# buz_schematic.net
KiCad netlist of a schematic drawn in Altium Designer
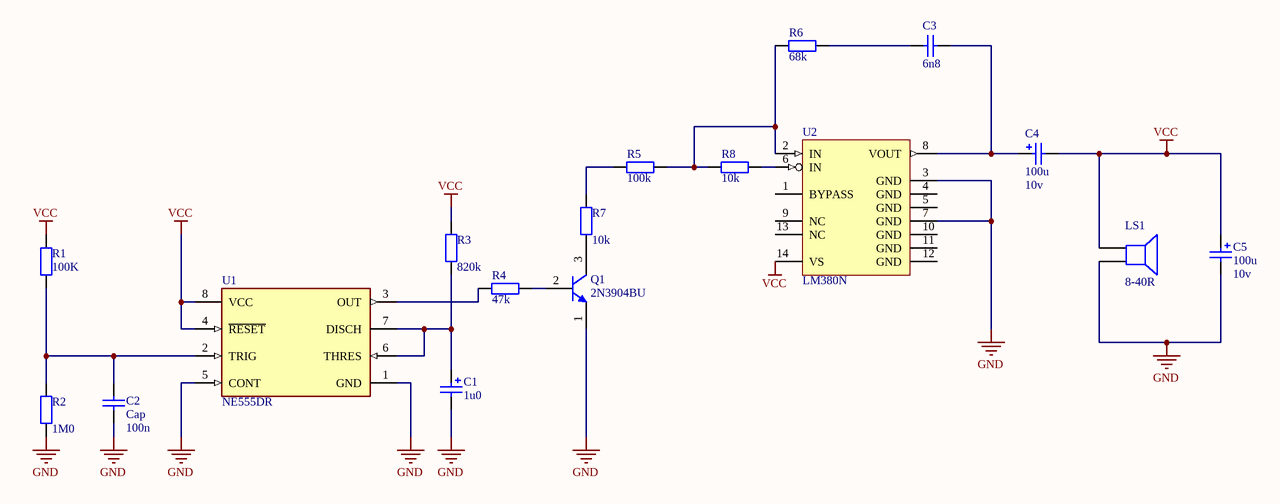
[diagram p0: buz_schematic.SchDoc]

(export (version "E")
  (design (tool "Eeschema 10.0.6"))
  (components
    (comp (ref "C1")
      (value "1u0")
      (footprint "RB7.6-15")
      (description "Polarized Capacitor (Radial)")
      (fields (field (name "PUBLISHER") "Altium Limited"))
      (libsource (lib "DBUZ_Integrated_Library") (part "Cap Pol1"))
    )
    (comp (ref "C2")
      (value "Cap")
      (footprint "RAD-0.3")
      (description "Capacitor")
      (fields (field (name "ALTIUM_VALUE") "100n") (field (name "PUBLISHER") "Altium Limited"))
      (libsource (lib "DBUZ_Integrated_Library") (part "Cap"))
    )
    (comp (ref "C3")
      (value "6n8")
      (footprint "RAD-0.3")
      (description "Capacitor")
      (fields (field (name "PUBLISHER") "Altium Limited"))
      (libsource (lib "DBUZ_Integrated_Library") (part "Cap"))
    )
    (comp (ref "C4")
      (value "100u")
      (footprint "RB7.6-15")
      (description "Polarized Capacitor (Radial)")
      (fields (field (name "ALTIUM_VALUE") "10v") (field (name "PUBLISHER") "Altium Limited"))
      (libsource (lib "DBUZ_Integrated_Library") (part "Cap Pol1"))
    )
    (comp (ref "C5")
      (value "100u")
      (footprint "RB7.6-15")
      (description "Polarized Capacitor (Radial)")
      (fields (field (name "ALTIUM_VALUE") "10v") (field (name "PUBLISHER") "Altium Limited"))
      (libsource (lib "DBUZ_Integrated_Library") (part "Cap Pol1"))
    )
    (comp (ref "LS1")
      (value "8-40R")
      (footprint "AXIAL-0.4")
      (description "Loudspeaker")
      (fields (field (name "PUBLISHER") "Altium Limited"))
      (libsource (lib "DBUZ_Integrated_Library") (part "Speaker"))
    )
    (comp (ref "Q1")
      (value "2N3904BU")
      (footprint "FAIR-TO-92")
      (description "NPN General-Purpose Amplifier, 40 V VCEO, 0.2 A, -55 to 150 degC, 2-Pin TO-92, RoHS, Bulk")
      (fields (field (name "MANUFACTURER") "FairchildSemiconductor"))
      (libsource (lib "DBUZ_Integrated_Library") (part "2N3904BU"))
    )
    (comp (ref "R1")
      (value "100K")
      (footprint "AXIAL-0.4")
      (description "Resistor")
      (fields (field (name "Comment") "Res2") (field (name "PUBLISHER") "Altium Limited"))
      (libsource (lib "") (part "Res2_2"))
    )
    (comp (ref "R2")
      (value "1M0")
      (footprint "AXIAL-0.4")
      (description "Resistor")
      (fields (field (name "Comment") "Res2") (field (name "PUBLISHER") "Altium Limited"))
      (libsource (lib "") (part "Res2_1"))
    )
    (comp (ref "R3")
      (value "820k")
      (footprint "AXIAL-0.4")
      (description "Resistor")
      (fields (field (name "Comment") "Res2") (field (name "PUBLISHER") "Altium Limited"))
      (libsource (lib "") (part "Res2_1"))
    )
    (comp (ref "R4")
      (value "47k")
      (footprint "AXIAL-0.4")
      (description "Resistor")
      (fields (field (name "Comment") "Res2") (field (name "PUBLISHER") "Altium Limited"))
      (libsource (lib "DBUZ_Integrated_Library") (part "Res2"))
    )
    (comp (ref "R5")
      (value "100k")
      (footprint "AXIAL-0.4")
      (description "Resistor")
      (fields (field (name "Comment") "Res2") (field (name "PUBLISHER") "Altium Limited"))
      (libsource (lib "DBUZ_Integrated_Library") (part "Res2"))
    )
    (comp (ref "R6")
      (value "68k")
      (footprint "AXIAL-0.4")
      (description "Resistor")
      (fields (field (name "Comment") "Res2") (field (name "PUBLISHER") "Altium Limited"))
      (libsource (lib "DBUZ_Integrated_Library") (part "Res2"))
    )
    (comp (ref "R7")
      (value "10k")
      (footprint "AXIAL-0.4")
      (description "Resistor")
      (fields (field (name "Comment") "Res2") (field (name "PUBLISHER") "Altium Limited"))
      (libsource (lib "") (part "Res2_1"))
    )
    (comp (ref "R8")
      (value "10k")
      (footprint "AXIAL-0.4")
      (description "Resistor")
      (fields (field (name "Comment") "Res2") (field (name "PUBLISHER") "Altium Limited"))
      (libsource (lib "DBUZ_Integrated_Library") (part "Res2"))
    )
    (comp (ref "U1")
      (value "NE555DR")
      (footprint "FP-D0008A-IPC_C")
      (description "IC OSC SGL TIMER 100KHZ 8-SOIC")
      (libsource (lib "DBUZ_Integrated_Library") (part "555"))
    )
    (comp (ref "U2")
      (value "LM380N")
      (footprint "N14A")
      (description "2.5W Audio Power Amplifier, 14-pin MDIP")
      (fields (field (name "MANUFACTURER") "National Semiconductor"))
      (libsource (lib "DB_ILib") (part "LM380N"))
    )
  )
  (nets
    (net (code "1") (name "GND") (class "Default")
      (node (ref "C1") (pin "2") (pinfunction "2_2") (pintype "passive"))
      (node (ref "C2") (pin "1") (pinfunction "1_1") (pintype "passive"))
      (node (ref "C5") (pin "2") (pinfunction "2_2") (pintype "passive"))
      (node (ref "LS1") (pin "2") (pinfunction "2_2") (pintype "passive"))
      (node (ref "Q1") (pin "1") (pinfunction "E_1") (pintype "passive"))
      (node (ref "R2") (pin "1") (pinfunction "1_1") (pintype "passive"))
      (node (ref "U1") (pin "1") (pinfunction "GND_1") (pintype "power_in"))
      (node (ref "U1") (pin "5") (pinfunction "CONT_5") (pintype "input"))
      (node (ref "U2") (pin "3") (pinfunction "GND_3") (pintype "power_in"))
      (node (ref "U2") (pin "7") (pinfunction "GND_7") (pintype "power_in"))
    )
    (net (code "2") (name "Net-(C3-Pad1)") (class "Default")
      (node (ref "C3") (pin "1") (pinfunction "1_1") (pintype "passive"))
      (node (ref "R6") (pin "1") (pinfunction "1_1") (pintype "passive"))
    )
    (net (code "3") (name "Net-(Q1-B)") (class "Default")
      (node (ref "Q1") (pin "2") (pinfunction "B_2") (pintype "passive"))
      (node (ref "R4") (pin "1") (pinfunction "1_1") (pintype "passive"))
    )
    (net (code "4") (name "Net-(Q1-C)") (class "Default")
      (node (ref "Q1") (pin "3") (pinfunction "C_3") (pintype "passive"))
      (node (ref "R7") (pin "1") (pinfunction "1_1") (pintype "passive"))
    )
    (net (code "5") (name "Net-(R5-Pad1)") (class "Default")
      (node (ref "R5") (pin "1") (pinfunction "1_1") (pintype "passive"))
      (node (ref "R6") (pin "2") (pinfunction "2_2") (pintype "passive"))
      (node (ref "R8") (pin "2") (pinfunction "2_2") (pintype "passive"))
      (node (ref "U2") (pin "2") (pinfunction "IN_2") (pintype "input"))
    )
    (net (code "6") (name "Net-(R5-Pad2)") (class "Default")
      (node (ref "R5") (pin "2") (pinfunction "2_2") (pintype "passive"))
      (node (ref "R7") (pin "2") (pinfunction "2_2") (pintype "passive"))
    )
    (net (code "7") (name "Net-(R8-Pad1)") (class "Default")
      (node (ref "R8") (pin "1") (pinfunction "1_1") (pintype "passive"))
      (node (ref "U2") (pin "6") (pinfunction "IN_6") (pintype "input"))
    )
    (net (code "8") (name "Net-(U1-DISCH)") (class "Default")
      (node (ref "C1") (pin "1") (pinfunction "1_1") (pintype "passive"))
      (node (ref "R3") (pin "1") (pinfunction "1_1") (pintype "passive"))
      (node (ref "U1") (pin "6") (pinfunction "THRES_6") (pintype "input"))
      (node (ref "U1") (pin "7") (pinfunction "DISCH_7") (pintype "open_collector"))
    )
    (net (code "9") (name "Net-(U1-OUT)") (class "Default")
      (node (ref "R4") (pin "2") (pinfunction "2_2") (pintype "passive"))
      (node (ref "U1") (pin "3") (pinfunction "OUT_3") (pintype "output"))
    )
    (net (code "10") (name "Net-(U1-TRIG)") (class "Default")
      (node (ref "C2") (pin "2") (pinfunction "2_2") (pintype "passive"))
      (node (ref "R1") (pin "2") (pinfunction "2_2") (pintype "passive"))
      (node (ref "R2") (pin "2") (pinfunction "2_2") (pintype "passive"))
      (node (ref "U1") (pin "2") (pinfunction "TRIG_2") (pintype "input"))
    )
    (net (code "11") (name "Net-(U2-VOUT)") (class "Default")
      (node (ref "C3") (pin "2") (pinfunction "2_2") (pintype "passive"))
      (node (ref "C4") (pin "1") (pinfunction "1_1") (pintype "passive"))
      (node (ref "U2") (pin "8") (pinfunction "VOUT_8") (pintype "output"))
    )
    (net (code "12") (name "VCC") (class "Default")
      (node (ref "C4") (pin "2") (pinfunction "2_2") (pintype "passive"))
      (node (ref "C5") (pin "1") (pinfunction "1_1") (pintype "passive"))
      (node (ref "LS1") (pin "1") (pinfunction "1_1") (pintype "passive"))
      (node (ref "R1") (pin "1") (pinfunction "1_1") (pintype "passive"))
      (node (ref "R3") (pin "2") (pinfunction "2_2") (pintype "passive"))
      (node (ref "U1") (pin "4") (pinfunction "~{RESET}_4") (pintype "input"))
      (node (ref "U1") (pin "8") (pinfunction "VCC_8") (pintype "power_in"))
      (node (ref "U2") (pin "14") (pinfunction "VS_14") (pintype "power_in"))
    )
    (net (code "13") (name "unconnected-(U2-BYPASS-Pad1)") (class "Default")
      (node (ref "U2") (pin "1") (pinfunction "BYPASS_1") (pintype "passive"))
    )
    (net (code "14") (name "unconnected-(U2-GND-Pad4)") (class "Default")
      (node (ref "U2") (pin "4") (pinfunction "GND_4") (pintype "power_in"))
    )
    (net (code "15") (name "unconnected-(U2-GND-Pad5)") (class "Default")
      (node (ref "U2") (pin "5") (pinfunction "GND_5") (pintype "power_in"))
    )
    (net (code "16") (name "unconnected-(U2-GND-Pad10)") (class "Default")
      (node (ref "U2") (pin "10") (pinfunction "GND_10") (pintype "power_in"))
    )
    (net (code "17") (name "unconnected-(U2-GND-Pad11)") (class "Default")
      (node (ref "U2") (pin "11") (pinfunction "GND_11") (pintype "power_in"))
    )
    (net (code "18") (name "unconnected-(U2-GND-Pad12)") (class "Default")
      (node (ref "U2") (pin "12") (pinfunction "GND_12") (pintype "power_in"))
    )
    (net (code "19") (name "unconnected-(U2-NC-Pad9)") (class "Default")
      (node (ref "U2") (pin "9") (pinfunction "NC_9") (pintype "passive"))
    )
    (net (code "20") (name "unconnected-(U2-NC-Pad13)") (class "Default")
      (node (ref "U2") (pin "13") (pinfunction "NC_13") (pintype "passive"))
    )
  )
)
